# BrauV2_Relay.net
KiCad netlist of a schematic drawn in Altium Designer
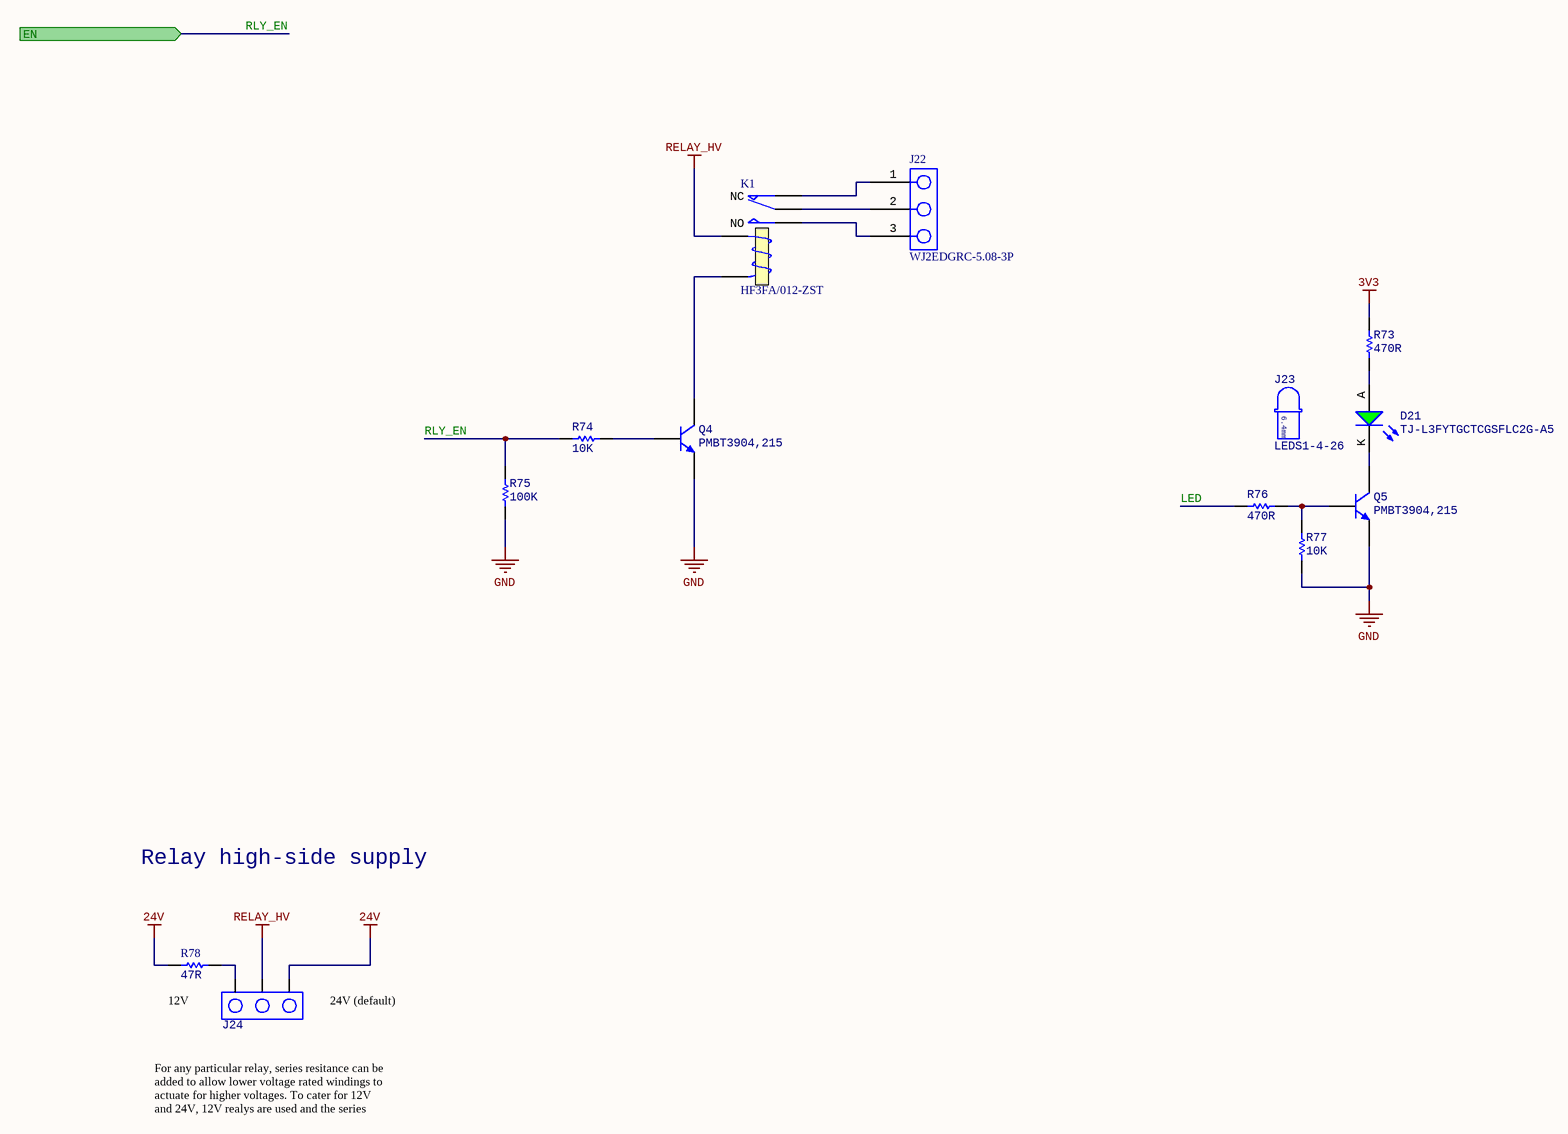
[diagram p0: BrauV2_Relay.SchDoc]

(export (version "E")
  (design (tool "Eeschema 10.0.6"))
  (components
    (comp (ref "D21")
      (value "TJ-L3FYTGCTCGSFLC2G-A5")
      (footprint "LED_3MM_SPACED_6.4MM_GREEN")
      (description "LED 3mm Green 515nm~530nm 1.8V~3.6V Through Hole Light Emitting Diodes (LED) RoHS C330751")
      (libsource (lib "BrauV2_Diode") (part "TJ-L3FYTGCTCGSFLC2G-A5"))
    )
    (comp (ref "J22")
      (value "WJ2EDGRC-5.08-3P")
      (footprint "796638-3")
      (description "Covered（4Sided） 3 1 0.200\"（5.08mm） 3 P=5.08mm Pluggable System Terminal Block RoHS")
      (libsource (lib "BrauV2_Connector") (part "WJ2EDGRC-5.08-3P"))
    )
    (comp (ref "J23")
      (value "LEDS1-4-26")
      (footprint "3MM_LED_SPACER_6.4MM")
      (description "3mm LED spacer 6.4mm height")
      (libsource (lib "BrauV2_Misc") (part "LEDS1-4-26"))
    )
    (comp (ref "J24")
      (value "12251103CNG0S115001")
      (footprint "Header_3POS")
      (description "Pin Header 3 1 right-angle，180degrees 2.54mm Through Hole,P=2.54mm Pin Header & Female Header RoHS")
      (libsource (lib "BrauV2_Connector") (part "3-way Jumper"))
    )
    (comp (ref "K1")
      (value "HF3FA/012-ZST")
      (footprint "HF3FA/012-ZST")
      (description "General Purpose Non Latching 12VDC SPDT Through Hole Relays RoHS")
      (libsource (lib "BrauV2_Misc") (part "RELAY_SPDT"))
    )
    (comp (ref "Q4")
      (value "PMBT3904,215")
      (footprint "SOT23-3")
      (description "NPN 200mA 40V 250mW SOT-23(SOT-23-3) Transistors (NPN/PNP) RoHS")
      (libsource (lib "BrauV2_Transistor") (part "PMBT3904,215"))
    )
    (comp (ref "Q5")
      (value "PMBT3904,215")
      (footprint "SOT23-3")
      (description "NPN 200mA 40V 250mW SOT-23(SOT-23-3) Transistors (NPN/PNP) RoHS")
      (libsource (lib "BrauV2_Transistor") (part "PMBT3904,215"))
    )
    (comp (ref "R73")
      (value "AC2512FK-07470RL")
      (footprint "SMD_RES_2512(6432)_N")
      (description "470Ω ±1% 1W ±100ppm/℃ 2512 Chip Resistor - Surface Mount RoHS")
      (fields (field (name "TOLERANCE") "1%") (field (name "RESISTANCE") "470R"))
      (libsource (lib "BrauV2_Resistor") (part "470R 2512 1% 1W"))
    )
    (comp (ref "R74")
      (value "RC0402FR-0710KL")
      (footprint "SMD_RES_0402(1005)_N")
      (description "10kΩ ±1% 1/16W ±100ppm/℃ 0402 Chip Resistor - Surface Mount RoHS")
      (fields (field (name "TOLERANCE") "1%") (field (name "RESISTANCE") "10K"))
      (libsource (lib "BrauV2_Resistor") (part "10K 0402 1% 1/16W"))
    )
    (comp (ref "R75")
      (value "RC0402FR-07100KL")
      (footprint "SMD_RES_0402(1005)_N")
      (description "100kΩ ±1% 1/16W ±100ppm/℃ 0402 Chip Resistor - Surface Mount RoHS")
      (fields (field (name "TOLERANCE") "1%") (field (name "RESISTANCE") "100K"))
      (libsource (lib "BrauV2_Resistor") (part "100K 0402 1% 1/16W"))
    )
    (comp (ref "R76")
      (value "AC2512FK-07470RL")
      (footprint "SMD_RES_2512(6432)_N")
      (description "470Ω ±1% 1W ±100ppm/℃ 2512 Chip Resistor - Surface Mount RoHS")
      (fields (field (name "TOLERANCE") "1%") (field (name "RESISTANCE") "470R"))
      (libsource (lib "BrauV2_Resistor") (part "470R 2512 1% 1W"))
    )
    (comp (ref "R77")
      (value "RC0402FR-0710KL")
      (footprint "SMD_RES_0402(1005)_N")
      (description "10kΩ ±1% 1/16W ±100ppm/℃ 0402 Chip Resistor - Surface Mount RoHS")
      (fields (field (name "TOLERANCE") "1%") (field (name "RESISTANCE") "10K"))
      (libsource (lib "BrauV2_Resistor") (part "10K 0402 1% 1/16W"))
    )
    (comp (ref "R78")
      (value "AC2512FK-0747RL")
      (footprint "SMD_RES_2512(6432)_N")
      (description "47Ω ±1% 1W ±100ppm/℃ 2512 Chip Resistor - Surface Mount RoHS")
      (fields (field (name "TOLERANCE") "1%") (field (name "RESISTANCE") "47R"))
      (libsource (lib "BrauV2_Resistor") (part "47R 2512 1% 1W"))
    )
  )
  (nets
    (net (code "1") (name "/LED") (class "Default")
      (node (ref "R76") (pin "2") (pinfunction "2_2") (pintype "passive"))
    )
    (net (code "2") (name "/RLY_EN") (class "Default")
      (node (ref "R74") (pin "2") (pinfunction "2_2") (pintype "passive"))
      (node (ref "R75") (pin "1") (pinfunction "1_1") (pintype "passive"))
    )
    (net (code "3") (name "3V3") (class "Default")
      (node (ref "R73") (pin "2") (pinfunction "2_2") (pintype "passive"))
    )
    (net (code "4") (name "24V") (class "Default")
      (node (ref "J24") (pin "1") (pinfunction "1_1") (pintype "passive"))
      (node (ref "R78") (pin "1") (pinfunction "1_1") (pintype "passive"))
    )
    (net (code "5") (name "GND") (class "Default")
      (node (ref "Q4") (pin "2") (pinfunction "E_2") (pintype "passive"))
      (node (ref "Q5") (pin "2") (pinfunction "E_2") (pintype "passive"))
      (node (ref "R75") (pin "2") (pinfunction "2_2") (pintype "passive"))
      (node (ref "R77") (pin "1") (pinfunction "1_1") (pintype "passive"))
    )
    (net (code "6") (name "Net-(D21-PadA)") (class "Default")
      (node (ref "D21") (pin "A") (pinfunction "A_A") (pintype "passive"))
      (node (ref "R73") (pin "1") (pinfunction "1_1") (pintype "passive"))
    )
    (net (code "7") (name "Net-(J24-Pad3)") (class "Default")
      (node (ref "J24") (pin "3") (pinfunction "3_3") (pintype "passive"))
      (node (ref "R78") (pin "2") (pinfunction "2_2") (pintype "passive"))
    )
    (net (code "8") (name "Net-(K1-COM)") (class "Default")
      (node (ref "J22") (pin "2") (pinfunction "2_2") (pintype "passive"))
      (node (ref "K1") (pin "1") (pinfunction "COM_1") (pintype "passive"))
    )
    (net (code "9") (name "Net-(K1-NC)") (class "Default")
      (node (ref "J22") (pin "1") (pinfunction "1_1") (pintype "passive"))
      (node (ref "K1") (pin "2") (pinfunction "NC_2") (pintype "passive"))
    )
    (net (code "10") (name "Net-(K1-NO)") (class "Default")
      (node (ref "J22") (pin "3") (pinfunction "3_3") (pintype "passive"))
      (node (ref "K1") (pin "3") (pinfunction "NO_3") (pintype "passive"))
    )
    (net (code "11") (name "Net-(K1-T2)") (class "Default")
      (node (ref "K1") (pin "5") (pinfunction "T2_5") (pintype "passive"))
      (node (ref "Q4") (pin "3") (pinfunction "C_3") (pintype "passive"))
    )
    (net (code "12") (name "Net-(Q4-B)") (class "Default")
      (node (ref "Q4") (pin "1") (pinfunction "B_1") (pintype "passive"))
      (node (ref "R74") (pin "1") (pinfunction "1_1") (pintype "passive"))
    )
    (net (code "13") (name "Net-(Q5-B)") (class "Default")
      (node (ref "Q5") (pin "1") (pinfunction "B_1") (pintype "passive"))
      (node (ref "R76") (pin "1") (pinfunction "1_1") (pintype "passive"))
      (node (ref "R77") (pin "2") (pinfunction "2_2") (pintype "passive"))
    )
    (net (code "14") (name "Net-(Q5-C)") (class "Default")
      (node (ref "D21") (pin "K") (pinfunction "K_K") (pintype "passive"))
      (node (ref "Q5") (pin "3") (pinfunction "C_3") (pintype "passive"))
    )
    (net (code "15") (name "RELAY_HV") (class "Default")
      (node (ref "J24") (pin "2") (pinfunction "2_2") (pintype "passive"))
      (node (ref "K1") (pin "4") (pinfunction "T1_4") (pintype "passive"))
    )
  )
)
